# Shore_Power.net
KiCad netlist of a schematic drawn in Altium Designer
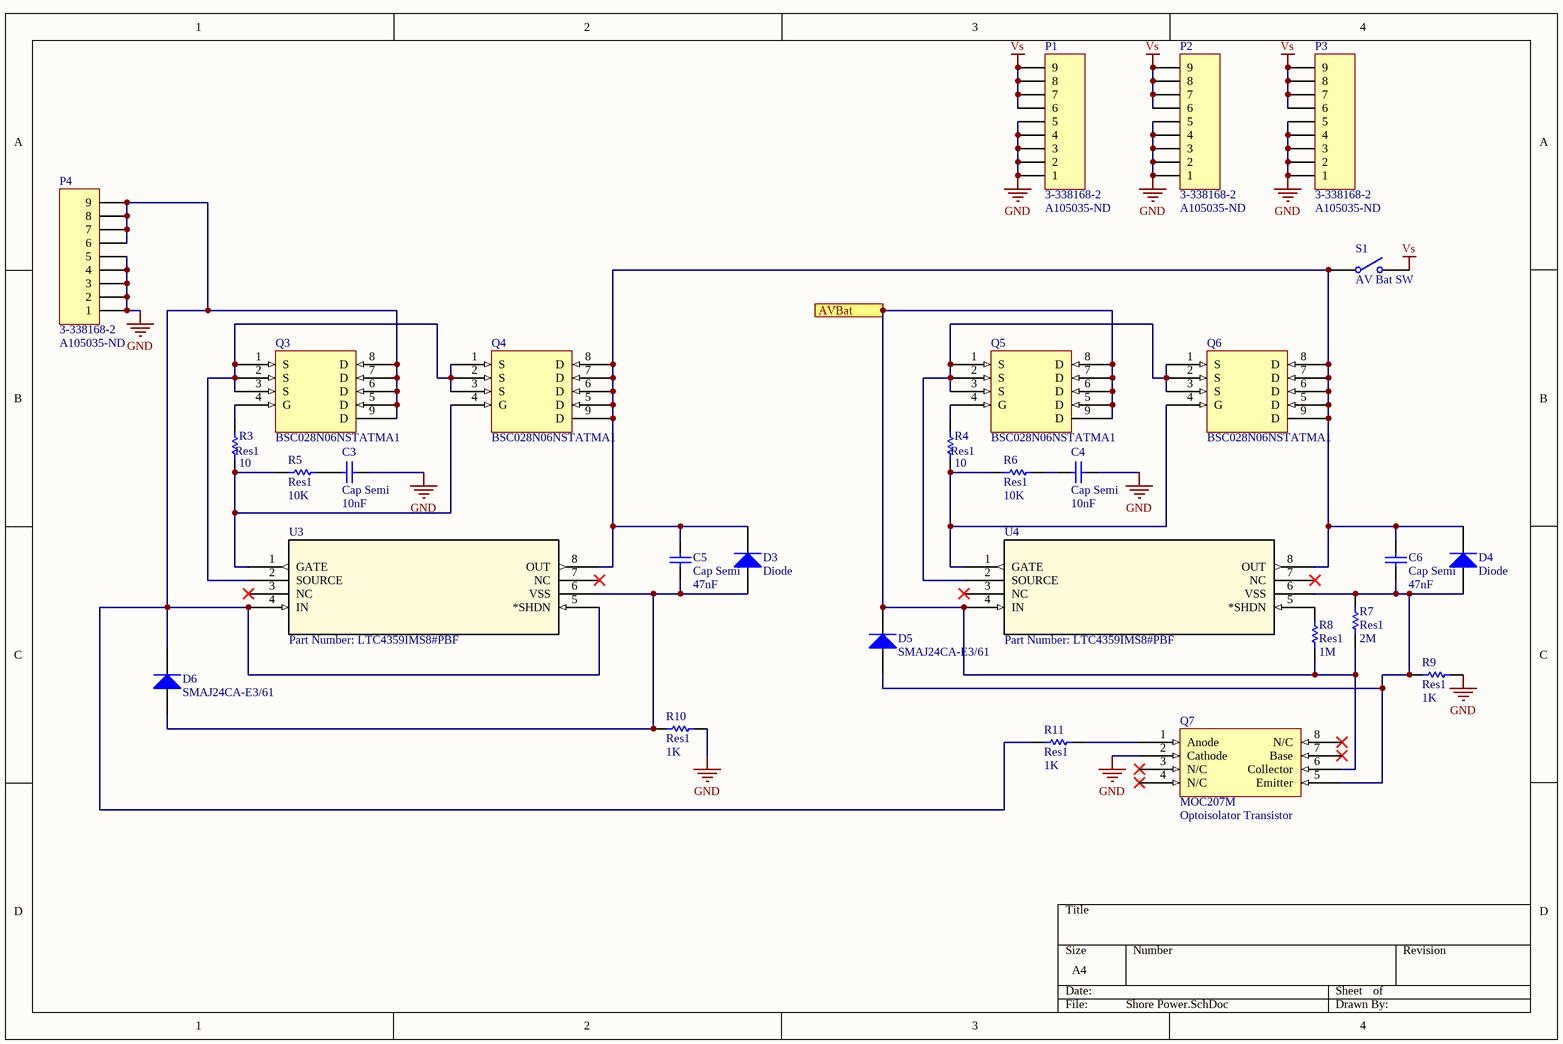
[diagram p0: Shore Power.SchDoc]

(export (version "E")
  (design (tool "Eeschema 10.0.6"))
  (components
    (comp (ref "C3")
      (value "Cap Semi")
      (footprint "C1206")
      (description "Capacitor (Semiconductor SIM Model)")
      (fields (field (name "ALTIUM_VALUE") "10nF") (field (name "PUBLISHER") "Altium Limited"))
      (libsource (lib "Miscellaneous Devices") (part "Cap Semi"))
    )
    (comp (ref "C4")
      (value "Cap Semi")
      (footprint "C1206")
      (description "Capacitor (Semiconductor SIM Model)")
      (fields (field (name "ALTIUM_VALUE") "10nF") (field (name "PUBLISHER") "Altium Limited"))
      (libsource (lib "Miscellaneous Devices") (part "Cap Semi"))
    )
    (comp (ref "C5")
      (value "Cap Semi")
      (footprint "C1206")
      (description "Capacitor (Semiconductor SIM Model)")
      (fields (field (name "ALTIUM_VALUE") "47nF") (field (name "PUBLISHER") "Altium Limited"))
      (libsource (lib "Miscellaneous Devices") (part "Cap Semi"))
    )
    (comp (ref "C6")
      (value "Cap Semi")
      (footprint "C1206")
      (description "Capacitor (Semiconductor SIM Model)")
      (fields (field (name "ALTIUM_VALUE") "47nF") (field (name "PUBLISHER") "Altium Limited"))
      (libsource (lib "Miscellaneous Devices") (part "Cap Semi"))
    )
    (comp (ref "D3")
      (value "Diode")
      (footprint "DIOM4427X27N")
      (description "Default Diode")
      (fields (field (name "PUBLISHER") "Altium Limited"))
      (libsource (lib "Miscellaneous Devices") (part "Diode"))
    )
    (comp (ref "D4")
      (value "Diode")
      (footprint "DIOM4427X27N")
      (description "Default Diode")
      (fields (field (name "PUBLISHER") "Altium Limited"))
      (libsource (lib "Miscellaneous Devices") (part "Diode"))
    )
    (comp (ref "D5")
      (value "SMAJ24CA-E3/61")
      (footprint "DIODE_DO-214AC")
      (description "Default Diode")
      (fields (field (name "PUBLISHER") "Altium Limited"))
      (libsource (lib "Miscellaneous Devices") (part "Diode"))
    )
    (comp (ref "D6")
      (value "SMAJ24CA-E3/61")
      (footprint "DIODE_DO-214AC")
      (description "Default Diode")
      (fields (field (name "PUBLISHER") "Altium Limited"))
      (libsource (lib "Miscellaneous Devices") (part "Diode"))
    )
    (comp (ref "P1")
      (value "3-338168-2")
      (footprint "CONN_3-338168-2")
      (description "Header, 9-Pin")
      (fields
        (field (name "SUPPLIER PART NUMBER 1") "A105035-ND")
        (field (name "PUBLISHER") "Altium Limited")
      )
      (libsource (lib "Miscellaneous Connectors") (part "Header 9"))
    )
    (comp (ref "P2")
      (value "3-338168-2")
      (footprint "CONN_3-338168-2")
      (description "Header, 9-Pin")
      (fields
        (field (name "SUPPLIER PART NUMBER 1") "A105035-ND")
        (field (name "PUBLISHER") "Altium Limited")
      )
      (libsource (lib "Miscellaneous Connectors") (part "Header 9"))
    )
    (comp (ref "P3")
      (value "3-338168-2")
      (footprint "CONN_3-338168-2")
      (description "Header, 9-Pin")
      (fields
        (field (name "SUPPLIER PART NUMBER 1") "A105035-ND")
        (field (name "PUBLISHER") "Altium Limited")
      )
      (libsource (lib "Miscellaneous Connectors") (part "Header 9"))
    )
    (comp (ref "P4")
      (value "3-338168-2")
      (footprint "CONN_3-338168-2")
      (description "Header, 9-Pin")
      (fields
        (field (name "SUPPLIER PART NUMBER 1") "A105035-ND")
        (field (name "PUBLISHER") "Altium Limited")
      )
      (libsource (lib "") (part "Header 9_1"))
    )
    (comp (ref "Q3")
      (value "BSC028N06NSTATMA1")
      (footprint "FDMS86101A")
      (description "MOSFET N-CH 100V 13A POWER56")
      (libsource (lib "FDMS86101A") (part "FDMS86101A"))
    )
    (comp (ref "Q4")
      (value "BSC028N06NSTATMA1")
      (footprint "FDMS86101A")
      (description "MOSFET N-CH 100V 13A POWER56")
      (libsource (lib "FDMS86101A") (part "FDMS86101A"))
    )
    (comp (ref "Q5")
      (value "BSC028N06NSTATMA1")
      (footprint "FDMS86101A")
      (description "MOSFET N-CH 100V 13A POWER56")
      (libsource (lib "FDMS86101A") (part "FDMS86101A"))
    )
    (comp (ref "Q6")
      (value "BSC028N06NSTATMA1")
      (footprint "FDMS86101A")
      (description "MOSFET N-CH 100V 13A POWER56")
      (libsource (lib "FDMS86101A") (part "FDMS86101A"))
    )
    (comp (ref "Q7")
      (value "MOC207M")
      (footprint "SOIC127P590X363-8N")
      (description "Optoisolator Transistor")
      (fields (field (name "DESC") "Optoisolator Transistor"))
      (libsource (lib "MOC207M") (part "MOC207M"))
    )
    (comp (ref "R3")
      (value "Res1")
      (footprint "6-0805_L")
      (description "Resistor")
      (fields (field (name "ALTIUM_VALUE") "10") (field (name "PUBLISHER") "Altium Limited"))
      (libsource (lib "Miscellaneous Devices") (part "Res1"))
    )
    (comp (ref "R4")
      (value "Res1")
      (footprint "6-0805_L")
      (description "Resistor")
      (fields (field (name "ALTIUM_VALUE") "10") (field (name "PUBLISHER") "Altium Limited"))
      (libsource (lib "Miscellaneous Devices") (part "Res1"))
    )
    (comp (ref "R5")
      (value "Res1")
      (footprint "6-0805_L")
      (description "Resistor")
      (fields (field (name "ALTIUM_VALUE") "10K") (field (name "PUBLISHER") "Altium Limited"))
      (libsource (lib "Miscellaneous Devices") (part "Res1"))
    )
    (comp (ref "R6")
      (value "Res1")
      (footprint "6-0805_L")
      (description "Resistor")
      (fields (field (name "ALTIUM_VALUE") "10K") (field (name "PUBLISHER") "Altium Limited"))
      (libsource (lib "Miscellaneous Devices") (part "Res1"))
    )
    (comp (ref "R7")
      (value "Res1")
      (footprint "J1-0603")
      (description "Resistor")
      (fields (field (name "ALTIUM_VALUE") "2M") (field (name "PUBLISHER") "Altium Limited"))
      (libsource (lib "Miscellaneous Devices") (part "Res1"))
    )
    (comp (ref "R8")
      (value "Res1")
      (footprint "J1-0603")
      (description "Resistor")
      (fields (field (name "ALTIUM_VALUE") "1M") (field (name "PUBLISHER") "Altium Limited"))
      (libsource (lib "Miscellaneous Devices") (part "Res1"))
    )
    (comp (ref "R9")
      (value "Res1")
      (footprint "STA_RMCF2512")
      (description "Resistor")
      (fields (field (name "ALTIUM_VALUE") "1K") (field (name "PUBLISHER") "Altium Limited"))
      (libsource (lib "Miscellaneous Devices") (part "Res1"))
    )
    (comp (ref "R10")
      (value "Res1")
      (footprint "STA_RMCF2512")
      (description "Resistor")
      (fields (field (name "ALTIUM_VALUE") "1K") (field (name "PUBLISHER") "Altium Limited"))
      (libsource (lib "Miscellaneous Devices") (part "Res1"))
    )
    (comp (ref "R11")
      (value "Res1")
      (footprint "STA_RMCF2512")
      (description "Resistor")
      (fields (field (name "ALTIUM_VALUE") "1K") (field (name "PUBLISHER") "Altium Limited"))
      (libsource (lib "Miscellaneous Devices") (part "Res1"))
    )
    (comp (ref "S1")
      (value "AV Bat SW")
      (footprint "M80-5000000M5-02-333-00-000")
      (description "Single-Pole, Single-Throw Switch")
      (fields (field (name "PUBLISHER") "Altium Limited"))
      (libsource (lib "Miscellaneous Devices") (part "SW-SPST"))
    )
    (comp (ref "U3")
      (value "Part Number: LTC4359IMS8#PBF")
      (footprint "MSOP-8_MS")
      (description "No Description Available")
      (fields
        (field (name "MANUFACTURER_PART_NUMBER") "LTC4359IMS8#PBF")
        (field (name "COPYRIGHT") "Copyright (C) 2018 Accelerated Designs. All rights reserved")
      )
      (libsource (lib "LTC4359IMS8#PBF") (part "LTC4359IMS8#PBF"))
    )
    (comp (ref "U4")
      (value "Part Number: LTC4359IMS8#PBF")
      (footprint "MSOP-8_MS")
      (description "No Description Available")
      (fields
        (field (name "MANUFACTURER_PART_NUMBER") "LTC4359IMS8#PBF")
        (field (name "COPYRIGHT") "Copyright (C) 2018 Accelerated Designs. All rights reserved")
      )
      (libsource (lib "LTC4359IMS8#PBF") (part "LTC4359IMS8#PBF"))
    )
  )
  (nets
    (net (code "1") (name "/AVBat") (class "Default")
      (node (ref "D5") (pin "2") (pinfunction "K_2") (pintype "passive"))
      (node (ref "Q5") (pin "5") (pinfunction "D_5") (pintype "input"))
      (node (ref "Q5") (pin "6") (pinfunction "D_6") (pintype "input"))
      (node (ref "Q5") (pin "7") (pinfunction "D_7") (pintype "input"))
      (node (ref "Q5") (pin "8") (pinfunction "D_8") (pintype "input"))
      (node (ref "Q5") (pin "9") (pinfunction "D_9") (pintype "passive"))
      (node (ref "Q7") (pin "6") (pinfunction "Collector_6") (pintype "input"))
      (node (ref "R7") (pin "1") (pinfunction "1_1") (pintype "passive"))
      (node (ref "R8") (pin "2") (pinfunction "2_2") (pintype "passive"))
      (node (ref "U4") (pin "4") (pinfunction "IN_4") (pintype "input"))
    )
    (net (code "2") (name "GND") (class "Default")
      (node (ref "C3") (pin "1") (pinfunction "1_1") (pintype "passive"))
      (node (ref "C4") (pin "1") (pinfunction "1_1") (pintype "passive"))
      (node (ref "P1") (pin "1") (pinfunction "1_1") (pintype "passive"))
      (node (ref "P1") (pin "2") (pinfunction "2_2") (pintype "passive"))
      (node (ref "P1") (pin "3") (pinfunction "3_3") (pintype "passive"))
      (node (ref "P1") (pin "4") (pinfunction "4_4") (pintype "passive"))
      (node (ref "P1") (pin "5") (pinfunction "5_5") (pintype "passive"))
      (node (ref "P2") (pin "1") (pinfunction "1_1") (pintype "passive"))
      (node (ref "P2") (pin "2") (pinfunction "2_2") (pintype "passive"))
      (node (ref "P2") (pin "3") (pinfunction "3_3") (pintype "passive"))
      (node (ref "P2") (pin "4") (pinfunction "4_4") (pintype "passive"))
      (node (ref "P2") (pin "5") (pinfunction "5_5") (pintype "passive"))
      (node (ref "P3") (pin "1") (pinfunction "1_1") (pintype "passive"))
      (node (ref "P3") (pin "2") (pinfunction "2_2") (pintype "passive"))
      (node (ref "P3") (pin "3") (pinfunction "3_3") (pintype "passive"))
      (node (ref "P3") (pin "4") (pinfunction "4_4") (pintype "passive"))
      (node (ref "P3") (pin "5") (pinfunction "5_5") (pintype "passive"))
      (node (ref "P4") (pin "1") (pinfunction "1_1") (pintype "passive"))
      (node (ref "P4") (pin "2") (pinfunction "2_2") (pintype "passive"))
      (node (ref "P4") (pin "3") (pinfunction "3_3") (pintype "passive"))
      (node (ref "P4") (pin "4") (pinfunction "4_4") (pintype "passive"))
      (node (ref "P4") (pin "5") (pinfunction "5_5") (pintype "passive"))
      (node (ref "Q7") (pin "2") (pinfunction "Cathode_2") (pintype "input"))
      (node (ref "R10") (pin "1") (pinfunction "1_1") (pintype "passive"))
      (node (ref "R9") (pin "1") (pinfunction "1_1") (pintype "passive"))
    )
    (net (code "3") (name "Net-(C3-Pad2)") (class "Default")
      (node (ref "C3") (pin "2") (pinfunction "2_2") (pintype "passive"))
      (node (ref "R5") (pin "2") (pinfunction "2_2") (pintype "passive"))
    )
    (net (code "4") (name "Net-(C4-Pad2)") (class "Default")
      (node (ref "C4") (pin "2") (pinfunction "2_2") (pintype "passive"))
      (node (ref "R6") (pin "2") (pinfunction "2_2") (pintype "passive"))
    )
    (net (code "5") (name "Net-(D3-A)") (class "Default")
      (node (ref "C5") (pin "2") (pinfunction "2_2") (pintype "passive"))
      (node (ref "D3") (pin "1") (pinfunction "A_1") (pintype "passive"))
      (node (ref "D6") (pin "1") (pinfunction "A_1") (pintype "passive"))
      (node (ref "R10") (pin "2") (pinfunction "2_2") (pintype "passive"))
      (node (ref "U3") (pin "6") (pinfunction "VSS_6") (pintype "power_in"))
    )
    (net (code "6") (name "Net-(D3-K)") (class "Default")
      (node (ref "C5") (pin "1") (pinfunction "1_1") (pintype "passive"))
      (node (ref "C6") (pin "1") (pinfunction "1_1") (pintype "passive"))
      (node (ref "D3") (pin "2") (pinfunction "K_2") (pintype "passive"))
      (node (ref "D4") (pin "2") (pinfunction "K_2") (pintype "passive"))
      (node (ref "Q4") (pin "5") (pinfunction "D_5") (pintype "input"))
      (node (ref "Q4") (pin "6") (pinfunction "D_6") (pintype "input"))
      (node (ref "Q4") (pin "7") (pinfunction "D_7") (pintype "input"))
      (node (ref "Q4") (pin "8") (pinfunction "D_8") (pintype "input"))
      (node (ref "Q4") (pin "9") (pinfunction "D_9") (pintype "passive"))
      (node (ref "Q6") (pin "5") (pinfunction "D_5") (pintype "input"))
      (node (ref "Q6") (pin "6") (pinfunction "D_6") (pintype "input"))
      (node (ref "Q6") (pin "7") (pinfunction "D_7") (pintype "input"))
      (node (ref "Q6") (pin "8") (pinfunction "D_8") (pintype "input"))
      (node (ref "Q6") (pin "9") (pinfunction "D_9") (pintype "passive"))
      (node (ref "S1") (pin "1") (pinfunction "COMMON_1") (pintype "passive"))
      (node (ref "U3") (pin "8") (pinfunction "OUT_8") (pintype "output"))
      (node (ref "U4") (pin "8") (pinfunction "OUT_8") (pintype "output"))
    )
    (net (code "7") (name "Net-(D4-A)") (class "Default")
      (node (ref "C6") (pin "2") (pinfunction "2_2") (pintype "passive"))
      (node (ref "D4") (pin "1") (pinfunction "A_1") (pintype "passive"))
      (node (ref "D5") (pin "1") (pinfunction "A_1") (pintype "passive"))
      (node (ref "Q7") (pin "5") (pinfunction "Emitter_5") (pintype "input"))
      (node (ref "R7") (pin "2") (pinfunction "2_2") (pintype "passive"))
      (node (ref "R9") (pin "2") (pinfunction "2_2") (pintype "passive"))
      (node (ref "U4") (pin "6") (pinfunction "VSS_6") (pintype "power_in"))
    )
    (net (code "8") (name "Net-(D6-K)") (class "Default")
      (node (ref "D6") (pin "2") (pinfunction "K_2") (pintype "passive"))
      (node (ref "P4") (pin "6") (pinfunction "6_6") (pintype "passive"))
      (node (ref "P4") (pin "7") (pinfunction "7_7") (pintype "passive"))
      (node (ref "P4") (pin "8") (pinfunction "8_8") (pintype "passive"))
      (node (ref "P4") (pin "9") (pinfunction "9_9") (pintype "passive"))
      (node (ref "Q3") (pin "5") (pinfunction "D_5") (pintype "input"))
      (node (ref "Q3") (pin "6") (pinfunction "D_6") (pintype "input"))
      (node (ref "Q3") (pin "7") (pinfunction "D_7") (pintype "input"))
      (node (ref "Q3") (pin "8") (pinfunction "D_8") (pintype "input"))
      (node (ref "Q3") (pin "9") (pinfunction "D_9") (pintype "passive"))
      (node (ref "R11") (pin "2") (pinfunction "2_2") (pintype "passive"))
      (node (ref "U3") (pin "4") (pinfunction "IN_4") (pintype "input"))
      (node (ref "U3") (pin "5") (pinfunction "*SHDN_5") (pintype "input"))
    )
    (net (code "9") (name "Net-(Q3-G)") (class "Default")
      (node (ref "Q3") (pin "4") (pinfunction "G_4") (pintype "input"))
      (node (ref "R3") (pin "2") (pinfunction "2_2") (pintype "passive"))
    )
    (net (code "10") (name "Net-(Q4-G)") (class "Default")
      (node (ref "Q4") (pin "4") (pinfunction "G_4") (pintype "input"))
      (node (ref "R3") (pin "1") (pinfunction "1_1") (pintype "passive"))
      (node (ref "R5") (pin "1") (pinfunction "1_1") (pintype "passive"))
      (node (ref "U3") (pin "1") (pinfunction "GATE_1") (pintype "output"))
    )
    (net (code "11") (name "Net-(Q5-G)") (class "Default")
      (node (ref "Q5") (pin "4") (pinfunction "G_4") (pintype "input"))
      (node (ref "R4") (pin "2") (pinfunction "2_2") (pintype "passive"))
    )
    (net (code "12") (name "Net-(Q6-G)") (class "Default")
      (node (ref "Q6") (pin "4") (pinfunction "G_4") (pintype "input"))
      (node (ref "R4") (pin "1") (pinfunction "1_1") (pintype "passive"))
      (node (ref "R6") (pin "1") (pinfunction "1_1") (pintype "passive"))
      (node (ref "U4") (pin "1") (pinfunction "GATE_1") (pintype "output"))
    )
    (net (code "13") (name "Net-(Q7-Anode)") (class "Default")
      (node (ref "Q7") (pin "1") (pinfunction "Anode_1") (pintype "input"))
      (node (ref "R11") (pin "1") (pinfunction "1_1") (pintype "passive"))
    )
    (net (code "14") (name "Net-(U3-SOURCE)") (class "Default")
      (node (ref "Q3") (pin "1") (pinfunction "S_1") (pintype "input"))
      (node (ref "Q3") (pin "2") (pinfunction "S_2") (pintype "input"))
      (node (ref "Q3") (pin "3") (pinfunction "S_3") (pintype "input"))
      (node (ref "Q4") (pin "1") (pinfunction "S_1") (pintype "input"))
      (node (ref "Q4") (pin "2") (pinfunction "S_2") (pintype "input"))
      (node (ref "Q4") (pin "3") (pinfunction "S_3") (pintype "input"))
      (node (ref "U3") (pin "2") (pinfunction "SOURCE_2") (pintype "passive"))
    )
    (net (code "15") (name "Net-(U4-*SHDN)") (class "Default")
      (node (ref "R8") (pin "1") (pinfunction "1_1") (pintype "passive"))
      (node (ref "U4") (pin "5") (pinfunction "*SHDN_5") (pintype "input"))
    )
    (net (code "16") (name "Net-(U4-SOURCE)") (class "Default")
      (node (ref "Q5") (pin "1") (pinfunction "S_1") (pintype "input"))
      (node (ref "Q5") (pin "2") (pinfunction "S_2") (pintype "input"))
      (node (ref "Q5") (pin "3") (pinfunction "S_3") (pintype "input"))
      (node (ref "Q6") (pin "1") (pinfunction "S_1") (pintype "input"))
      (node (ref "Q6") (pin "2") (pinfunction "S_2") (pintype "input"))
      (node (ref "Q6") (pin "3") (pinfunction "S_3") (pintype "input"))
      (node (ref "U4") (pin "2") (pinfunction "SOURCE_2") (pintype "passive"))
    )
    (net (code "17") (name "Vs") (class "Default")
      (node (ref "P1") (pin "6") (pinfunction "6_6") (pintype "passive"))
      (node (ref "P1") (pin "7") (pinfunction "7_7") (pintype "passive"))
      (node (ref "P1") (pin "8") (pinfunction "8_8") (pintype "passive"))
      (node (ref "P1") (pin "9") (pinfunction "9_9") (pintype "passive"))
      (node (ref "P2") (pin "6") (pinfunction "6_6") (pintype "passive"))
      (node (ref "P2") (pin "7") (pinfunction "7_7") (pintype "passive"))
      (node (ref "P2") (pin "8") (pinfunction "8_8") (pintype "passive"))
      (node (ref "P2") (pin "9") (pinfunction "9_9") (pintype "passive"))
      (node (ref "P3") (pin "6") (pinfunction "6_6") (pintype "passive"))
      (node (ref "P3") (pin "7") (pinfunction "7_7") (pintype "passive"))
      (node (ref "P3") (pin "8") (pinfunction "8_8") (pintype "passive"))
      (node (ref "P3") (pin "9") (pinfunction "9_9") (pintype "passive"))
      (node (ref "S1") (pin "2") (pinfunction "NO_2") (pintype "passive"))
    )
    (net (code "18") (name "unconnected-(Q7-Base-Pad7)") (class "Default")
      (node (ref "Q7") (pin "7") (pinfunction "Base_7") (pintype "input+no_connect"))
    )
    (net (code "19") (name "unconnected-(Q7-N{slash}C-Pad3)") (class "Default")
      (node (ref "Q7") (pin "3") (pinfunction "N/C_3") (pintype "input+no_connect"))
    )
    (net (code "20") (name "unconnected-(Q7-N{slash}C-Pad4)") (class "Default")
      (node (ref "Q7") (pin "4") (pinfunction "N/C_4") (pintype "input+no_connect"))
    )
    (net (code "21") (name "unconnected-(Q7-N{slash}C-Pad8)") (class "Default")
      (node (ref "Q7") (pin "8") (pinfunction "N/C_8") (pintype "input+no_connect"))
    )
    (net (code "22") (name "unconnected-(U3-NC-Pad3)") (class "Default")
      (node (ref "U3") (pin "3") (pinfunction "NC_3") (pintype "passive+no_connect"))
    )
    (net (code "23") (name "unconnected-(U3-NC-Pad7)") (class "Default")
      (node (ref "U3") (pin "7") (pinfunction "NC_7") (pintype "passive+no_connect"))
    )
    (net (code "24") (name "unconnected-(U4-NC-Pad3)") (class "Default")
      (node (ref "U4") (pin "3") (pinfunction "NC_3") (pintype "passive+no_connect"))
    )
    (net (code "25") (name "unconnected-(U4-NC-Pad7)") (class "Default")
      (node (ref "U4") (pin "7") (pinfunction "NC_7") (pintype "passive+no_connect"))
    )
  )
)
